# Presencia_Agua.net
KiCad netlist of a schematic drawn in Altium Designer
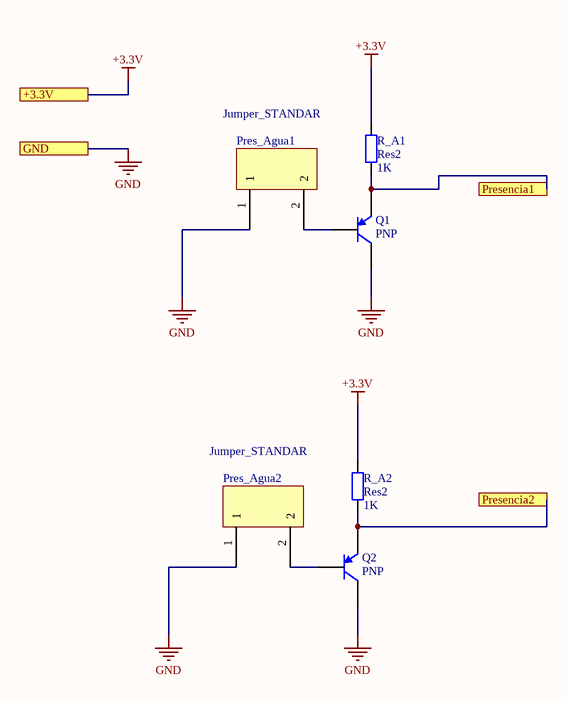
[diagram p0: Presencia_Agua.SchDoc]

(export (version "E")
  (design (tool "Eeschema 10.0.6"))
  (components
    (comp (ref "Pres_Agua1")
      (value "Jumper_STANDAR")
      (footprint "HDR1X2H")
      (libsource (lib "XSUB_COMP") (part "Jumper_STANDAR"))
    )
    (comp (ref "Pres_Agua2")
      (value "Jumper_STANDAR")
      (footprint "HDR1X2H")
      (libsource (lib "XSUB_COMP") (part "Jumper_STANDAR"))
    )
    (comp (ref "Q1")
      (value "PNP")
      (footprint "TO-92A")
      (description "PNP Bipolar Transistor")
      (fields (field (name "PUBLISHER") "Altium Limited"))
      (libsource (lib "Miscellaneous Devices") (part "PNP"))
    )
    (comp (ref "Q2")
      (value "PNP")
      (footprint "TO-92A")
      (description "PNP Bipolar Transistor")
      (fields (field (name "PUBLISHER") "Altium Limited"))
      (libsource (lib "Miscellaneous Devices") (part "PNP"))
    )
    (comp (ref "R_A1")
      (value "Res2")
      (footprint "AXIAL-0.4")
      (description "Resistor")
      (fields (field (name "ALTIUM_VALUE") "1K") (field (name "PUBLISHER") "Altium Limited"))
      (libsource (lib "Miscellaneous Devices") (part "Res2"))
    )
    (comp (ref "R_A2")
      (value "Res2")
      (footprint "AXIAL-0.4")
      (description "Resistor")
      (fields (field (name "ALTIUM_VALUE") "1K") (field (name "PUBLISHER") "Altium Limited"))
      (libsource (lib "Miscellaneous Devices") (part "Res2"))
    )
  )
  (nets
    (net (code "1") (name "+3.3V") (class "Default")
      (node (ref "R_A1") (pin "2") (pinfunction "2_2") (pintype "passive"))
      (node (ref "R_A2") (pin "2") (pinfunction "2_2") (pintype "passive"))
    )
    (net (code "2") (name "/Presencia1") (class "Default")
      (node (ref "Q1") (pin "3") (pinfunction "E_3") (pintype "passive"))
      (node (ref "R_A1") (pin "1") (pinfunction "1_1") (pintype "passive"))
    )
    (net (code "3") (name "/Presencia2") (class "Default")
      (node (ref "Q2") (pin "3") (pinfunction "E_3") (pintype "passive"))
      (node (ref "R_A2") (pin "1") (pinfunction "1_1") (pintype "passive"))
    )
    (net (code "4") (name "GND") (class "Default")
      (node (ref "Pres_Agua1") (pin "1") (pinfunction "1_1") (pintype "passive"))
      (node (ref "Pres_Agua2") (pin "1") (pinfunction "1_1") (pintype "passive"))
      (node (ref "Q1") (pin "1") (pinfunction "C_1") (pintype "passive"))
      (node (ref "Q2") (pin "1") (pinfunction "C_1") (pintype "passive"))
    )
    (net (code "5") (name "Net-(Q1-B)") (class "Default")
      (node (ref "Pres_Agua1") (pin "2") (pinfunction "2_2") (pintype "passive"))
      (node (ref "Q1") (pin "2") (pinfunction "B_2") (pintype "passive"))
    )
    (net (code "6") (name "Net-(Q2-B)") (class "Default")
      (node (ref "Pres_Agua2") (pin "2") (pinfunction "2_2") (pintype "passive"))
      (node (ref "Q2") (pin "2") (pinfunction "B_2") (pintype "passive"))
    )
  )
)
